# yamaHACK.net
KiCad netlist of a schematic drawn in EAGLE
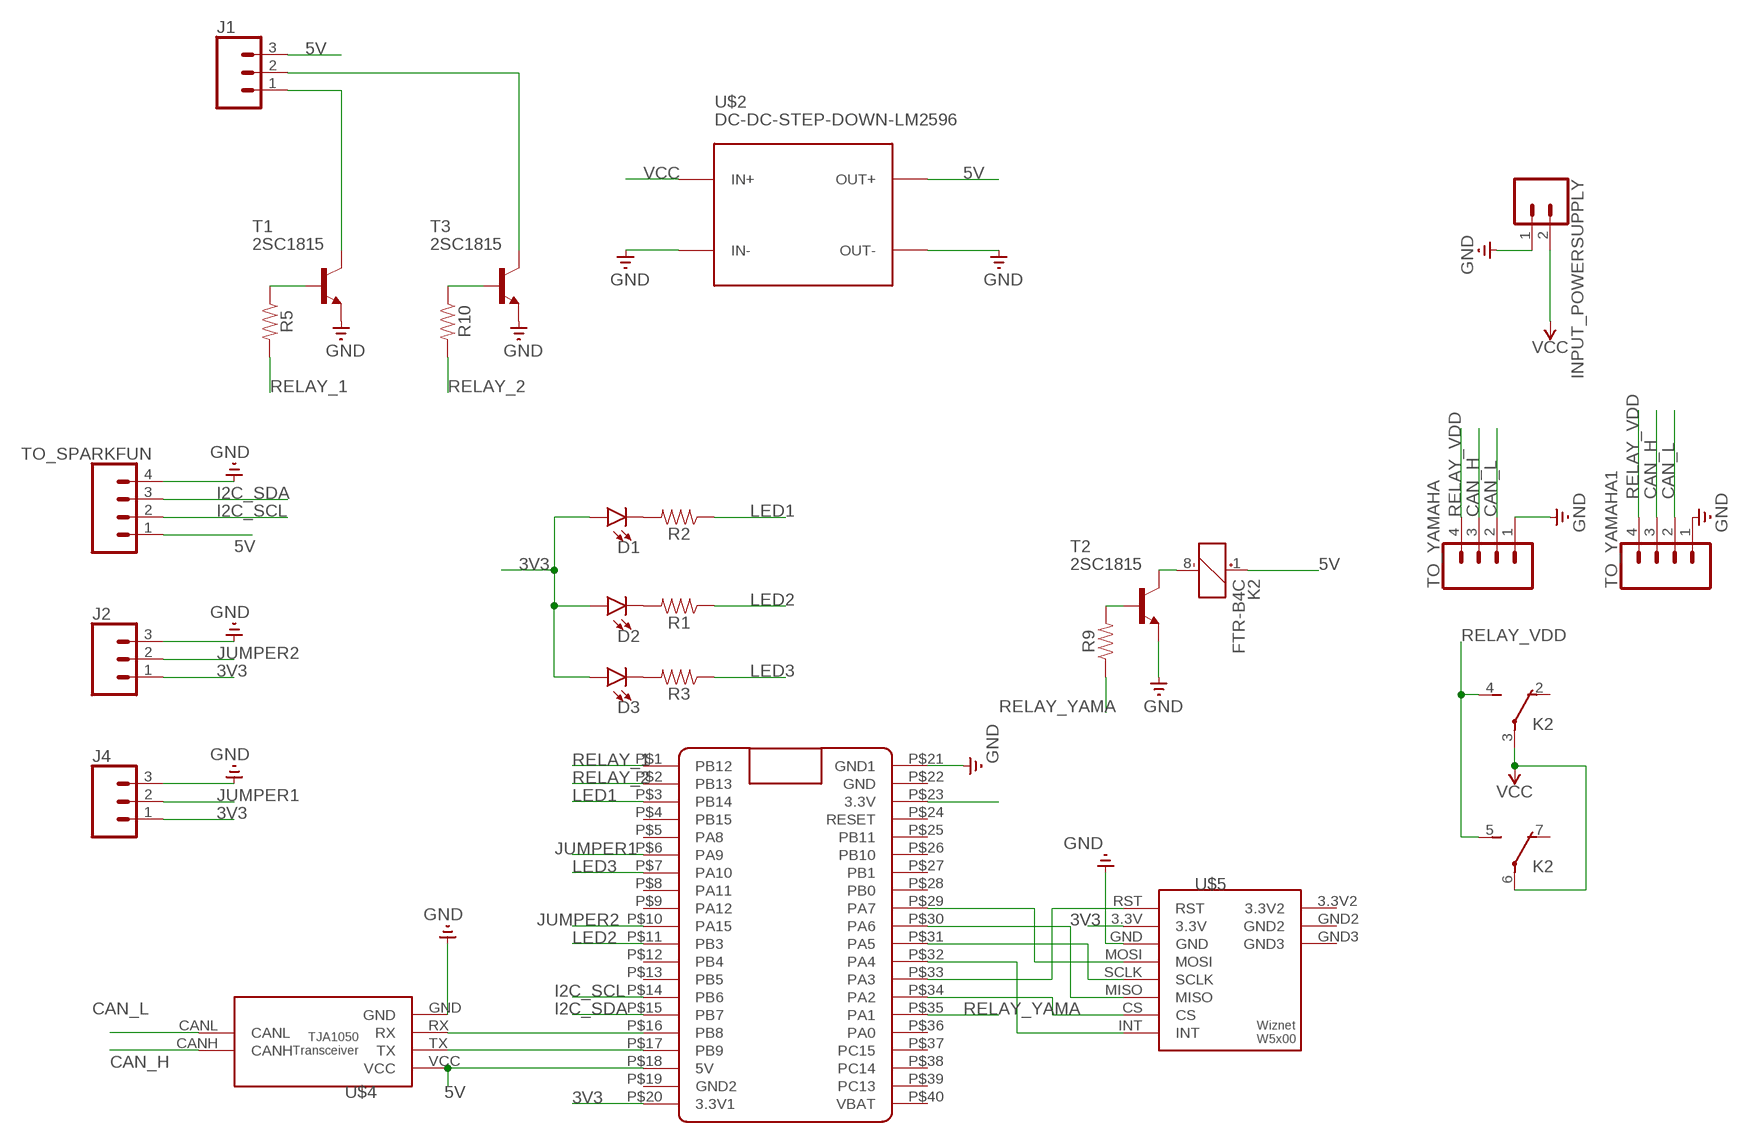
[diagram p0: schematic, sheet 1]

(export (version "E")
  (design (tool "Eeschema 10.0.6"))
  (components
    (comp (ref "D1")
      (value "LED3MM")
      (footprint "eagle-import:LED_3MM")
      (libsource (lib "eagle-import") (part "LED3MM"))
    )
    (comp (ref "D2")
      (value "LED3MM")
      (footprint "eagle-import:LED_3MM")
      (libsource (lib "eagle-import") (part "LED3MM"))
    )
    (comp (ref "D3")
      (value "LED3MM")
      (footprint "eagle-import:LED_3MM")
      (libsource (lib "eagle-import") (part "LED3MM"))
    )
    (comp (ref "INPUT_POWERSUPPLY")
      (value "CONN_02PTH3")
      (footprint "eagle-import:1X02_LONGPADS")
      (libsource (lib "eagle-import") (part "CONN_02PTH3"))
    )
    (comp (ref "J1")
      (value "CONN_03")
      (footprint "eagle-import:1X03")
      (libsource (lib "eagle-import") (part "CONN_03"))
    )
    (comp (ref "J2")
      (value "CONN_03")
      (footprint "eagle-import:1X03")
      (libsource (lib "eagle-import") (part "CONN_03"))
    )
    (comp (ref "J4")
      (value "CONN_03")
      (footprint "eagle-import:1X03")
      (libsource (lib "eagle-import") (part "CONN_03"))
    )
    (comp (ref "K2")
      (value "FTR-B4C")
      (footprint "eagle-import:FTR-B4C")
      (libsource (lib "eagle-import") (part "FTR-B4C"))
    )
    (comp (ref "R1")
      (value "RESISTORAXIAL-0.3")
      (footprint "eagle-import:AXIAL-0.3")
      (libsource (lib "eagle-import") (part "RESISTORAXIAL-0.3"))
    )
    (comp (ref "R2")
      (value "RESISTORAXIAL-0.3")
      (footprint "eagle-import:AXIAL-0.3")
      (libsource (lib "eagle-import") (part "RESISTORAXIAL-0.3"))
    )
    (comp (ref "R3")
      (value "RESISTORAXIAL-0.3")
      (footprint "eagle-import:AXIAL-0.3")
      (libsource (lib "eagle-import") (part "RESISTORAXIAL-0.3"))
    )
    (comp (ref "R5")
      (value "RESISTORAXIAL-0.3")
      (footprint "eagle-import:AXIAL-0.3")
      (libsource (lib "eagle-import") (part "RESISTORAXIAL-0.3"))
    )
    (comp (ref "R9")
      (value "RESISTORAXIAL-0.3")
      (footprint "eagle-import:AXIAL-0.3")
      (libsource (lib "eagle-import") (part "RESISTORAXIAL-0.3"))
    )
    (comp (ref "R10")
      (value "RESISTORAXIAL-0.3")
      (footprint "eagle-import:AXIAL-0.3")
      (libsource (lib "eagle-import") (part "RESISTORAXIAL-0.3"))
    )
    (comp (ref "T1")
      (value "2SC1815")
      (footprint "eagle-import:TO92-ECB")
      (libsource (lib "eagle-import") (part "2SC1815"))
    )
    (comp (ref "T2")
      (value "2SC1815")
      (footprint "eagle-import:TO92-ECB")
      (libsource (lib "eagle-import") (part "2SC1815"))
    )
    (comp (ref "T3")
      (value "2SC1815")
      (footprint "eagle-import:TO92-ECB")
      (libsource (lib "eagle-import") (part "2SC1815"))
    )
    (comp (ref "TO_SPARKFUN")
      (value "CONN_04")
      (footprint "eagle-import:1X04")
      (libsource (lib "eagle-import") (part "CONN_04"))
    )
    (comp (ref "TO_YAMAHA")
      (value "CONN_04")
      (footprint "eagle-import:1X04")
      (libsource (lib "eagle-import") (part "CONN_04"))
    )
    (comp (ref "TO_YAMAHA1")
      (value "CONN_04")
      (footprint "eagle-import:1X04")
      (libsource (lib "eagle-import") (part "CONN_04"))
    )
    (comp (ref "U$2")
      (value "DC-DC-STEP-DOWN-LM2596")
      (footprint "eagle-import:DC-DC-STEP-DOWN-LM2596")
      (libsource (lib "eagle-import") (part "DC-DC-STEP-DOWN-LM2596"))
    )
    (comp (ref "U$3")
      (value "BLUE_PILL")
      (footprint "eagle-import:BLUE_PILL")
      (libsource (lib "eagle-import") (part "BLUE_PILL"))
    )
    (comp (ref "U$4")
      (value "TJA1050TJA1050_WH")
      (footprint "eagle-import:TJA1050_WH")
      (libsource (lib "eagle-import") (part "TJA1050TJA1050_WH"))
    )
    (comp (ref "U$5")
      (value "WIZNET")
      (footprint "eagle-import:WIZNET_LITE")
      (libsource (lib "eagle-import") (part "WIZNET"))
    )
  )
  (nets
    (net (code "1") (name "/3V3") (class "Default")
      (node (ref "D1") (pin "A") (pinfunction "A_A") (pintype "passive"))
      (node (ref "D2") (pin "A") (pinfunction "A_A") (pintype "passive"))
      (node (ref "D3") (pin "A") (pinfunction "A_A") (pintype "passive"))
      (node (ref "J2") (pin "1") (pinfunction "1_1") (pintype "passive"))
      (node (ref "J4") (pin "1") (pinfunction "1_1") (pintype "passive"))
      (node (ref "U$3") (pin "P$20") (pinfunction "3.3V1_P$20") (pintype "bidirectional"))
      (node (ref "U$3") (pin "P$23") (pinfunction "3.3V_P$23") (pintype "bidirectional"))
      (node (ref "U$5") (pin "3.3V") (pinfunction "3.3V_3.3V") (pintype "bidirectional"))
    )
    (net (code "2") (name "/5V") (class "Default")
      (node (ref "J1") (pin "3") (pinfunction "3_3") (pintype "passive"))
      (node (ref "K2") (pin "1") (pinfunction "+_1") (pintype "passive"))
      (node (ref "TO_SPARKFUN") (pin "1") (pinfunction "1_1") (pintype "passive"))
      (node (ref "U$2") (pin "OUT+") (pinfunction "OUT+_OUT+") (pintype "bidirectional"))
      (node (ref "U$3") (pin "P$18") (pinfunction "5V_P$18") (pintype "bidirectional"))
      (node (ref "U$4") (pin "VCC") (pinfunction "VCC_VCC") (pintype "bidirectional"))
    )
    (net (code "3") (name "/CAN_H") (class "Default")
      (node (ref "TO_YAMAHA") (pin "3") (pinfunction "3_3") (pintype "passive"))
      (node (ref "TO_YAMAHA1") (pin "3") (pinfunction "3_3") (pintype "passive"))
      (node (ref "U$4") (pin "CANH") (pinfunction "CANH_CANH") (pintype "bidirectional"))
    )
    (net (code "4") (name "/CAN_L") (class "Default")
      (node (ref "TO_YAMAHA") (pin "2") (pinfunction "2_2") (pintype "passive"))
      (node (ref "TO_YAMAHA1") (pin "2") (pinfunction "2_2") (pintype "passive"))
      (node (ref "U$4") (pin "CANL") (pinfunction "CANL_CANL") (pintype "bidirectional"))
    )
    (net (code "5") (name "/I2C_SCL") (class "Default")
      (node (ref "TO_SPARKFUN") (pin "2") (pinfunction "2_2") (pintype "passive"))
      (node (ref "U$3") (pin "P$14") (pinfunction "PB6_P$14") (pintype "bidirectional"))
    )
    (net (code "6") (name "/I2C_SDA") (class "Default")
      (node (ref "TO_SPARKFUN") (pin "3") (pinfunction "3_3") (pintype "passive"))
      (node (ref "U$3") (pin "P$15") (pinfunction "PB7_P$15") (pintype "bidirectional"))
    )
    (net (code "7") (name "/JUMPER1") (class "Default")
      (node (ref "J4") (pin "2") (pinfunction "2_2") (pintype "passive"))
      (node (ref "U$3") (pin "P$6") (pinfunction "PA9_P$6") (pintype "bidirectional"))
    )
    (net (code "8") (name "/JUMPER2") (class "Default")
      (node (ref "J2") (pin "2") (pinfunction "2_2") (pintype "passive"))
      (node (ref "U$3") (pin "P$10") (pinfunction "PA15_P$10") (pintype "bidirectional"))
    )
    (net (code "9") (name "/LED1") (class "Default")
      (node (ref "R2") (pin "P$1") (pinfunction "1_P$1") (pintype "passive"))
      (node (ref "U$3") (pin "P$3") (pinfunction "PB14_P$3") (pintype "bidirectional"))
    )
    (net (code "10") (name "/LED2") (class "Default")
      (node (ref "R1") (pin "P$1") (pinfunction "1_P$1") (pintype "passive"))
      (node (ref "U$3") (pin "P$11") (pinfunction "PB3_P$11") (pintype "bidirectional"))
    )
    (net (code "11") (name "/LED3") (class "Default")
      (node (ref "R3") (pin "P$1") (pinfunction "1_P$1") (pintype "passive"))
      (node (ref "U$3") (pin "P$7") (pinfunction "PA10_P$7") (pintype "bidirectional"))
    )
    (net (code "12") (name "/RELAY_1") (class "Default")
      (node (ref "R5") (pin "P$2") (pinfunction "2_P$2") (pintype "passive"))
      (node (ref "U$3") (pin "P$1") (pinfunction "PB12_P$1") (pintype "bidirectional"))
    )
    (net (code "13") (name "/RELAY_2") (class "Default")
      (node (ref "R10") (pin "P$2") (pinfunction "2_P$2") (pintype "passive"))
      (node (ref "U$3") (pin "P$2") (pinfunction "PB13_P$2") (pintype "bidirectional"))
    )
    (net (code "14") (name "/RELAY_VDD") (class "Default")
      (node (ref "K2") (pin "4") (pinfunction "S_4") (pintype "passive"))
      (node (ref "K2") (pin "5") (pinfunction "S_5") (pintype "passive"))
      (node (ref "TO_YAMAHA") (pin "4") (pinfunction "4_4") (pintype "passive"))
      (node (ref "TO_YAMAHA1") (pin "4") (pinfunction "4_4") (pintype "passive"))
    )
    (net (code "15") (name "/RELAY_YAMA") (class "Default")
      (node (ref "R9") (pin "P$1") (pinfunction "1_P$1") (pintype "passive"))
      (node (ref "U$3") (pin "P$35") (pinfunction "PA1_P$35") (pintype "bidirectional"))
    )
    (net (code "16") (name "GND") (class "Default")
      (node (ref "INPUT_POWERSUPPLY") (pin "1") (pinfunction "1_1") (pintype "passive"))
      (node (ref "J2") (pin "3") (pinfunction "3_3") (pintype "passive"))
      (node (ref "J4") (pin "3") (pinfunction "3_3") (pintype "passive"))
      (node (ref "T1") (pin "E") (pinfunction "E_E") (pintype "passive"))
      (node (ref "T2") (pin "E") (pinfunction "E_E") (pintype "passive"))
      (node (ref "T3") (pin "E") (pinfunction "E_E") (pintype "passive"))
      (node (ref "TO_SPARKFUN") (pin "4") (pinfunction "4_4") (pintype "passive"))
      (node (ref "TO_YAMAHA") (pin "1") (pinfunction "1_1") (pintype "passive"))
      (node (ref "TO_YAMAHA1") (pin "1") (pinfunction "1_1") (pintype "passive"))
      (node (ref "U$2") (pin "IN-") (pinfunction "IN-_IN-") (pintype "bidirectional"))
      (node (ref "U$2") (pin "OUT-") (pinfunction "OUT-_OUT-") (pintype "bidirectional"))
      (node (ref "U$3") (pin "P$21") (pinfunction "GND1_P$21") (pintype "power_in"))
      (node (ref "U$4") (pin "GND") (pinfunction "GND_GND") (pintype "bidirectional"))
      (node (ref "U$5") (pin "GND") (pinfunction "GND_GND") (pintype "bidirectional"))
    )
    (net (code "17") (name "Net-(D1-C)") (class "Default")
      (node (ref "D1") (pin "K") (pinfunction "C_K") (pintype "passive"))
      (node (ref "R2") (pin "P$2") (pinfunction "2_P$2") (pintype "passive"))
    )
    (net (code "18") (name "Net-(D2-C)") (class "Default")
      (node (ref "D2") (pin "K") (pinfunction "C_K") (pintype "passive"))
      (node (ref "R1") (pin "P$2") (pinfunction "2_P$2") (pintype "passive"))
    )
    (net (code "19") (name "Net-(D3-C)") (class "Default")
      (node (ref "D3") (pin "K") (pinfunction "C_K") (pintype "passive"))
      (node (ref "R3") (pin "P$2") (pinfunction "2_P$2") (pintype "passive"))
    )
    (net (code "20") (name "Net-(J1-Pad1)") (class "Default")
      (node (ref "J1") (pin "1") (pinfunction "1_1") (pintype "passive"))
      (node (ref "T1") (pin "C") (pinfunction "C_C") (pintype "passive"))
    )
    (net (code "21") (name "Net-(J1-Pad2)") (class "Default")
      (node (ref "J1") (pin "2") (pinfunction "2_2") (pintype "passive"))
      (node (ref "T3") (pin "C") (pinfunction "C_C") (pintype "passive"))
    )
    (net (code "22") (name "Net-(K2C--)") (class "Default")
      (node (ref "K2") (pin "8") (pinfunction "-_8") (pintype "passive"))
      (node (ref "T2") (pin "C") (pinfunction "C_C") (pintype "passive"))
    )
    (net (code "23") (name "Net-(R5-1)") (class "Default")
      (node (ref "R5") (pin "P$1") (pinfunction "1_P$1") (pintype "passive"))
      (node (ref "T1") (pin "B") (pinfunction "B_B") (pintype "passive"))
    )
    (net (code "24") (name "Net-(R9-2)") (class "Default")
      (node (ref "R9") (pin "P$2") (pinfunction "2_P$2") (pintype "passive"))
      (node (ref "T2") (pin "B") (pinfunction "B_B") (pintype "passive"))
    )
    (net (code "25") (name "Net-(R10-1)") (class "Default")
      (node (ref "R10") (pin "P$1") (pinfunction "1_P$1") (pintype "passive"))
      (node (ref "T3") (pin "B") (pinfunction "B_B") (pintype "passive"))
    )
    (net (code "26") (name "Net-(U$3-PA2)") (class "Default")
      (node (ref "U$3") (pin "P$34") (pinfunction "PA2_P$34") (pintype "bidirectional"))
      (node (ref "U$5") (pin "CS") (pinfunction "CS_CS") (pintype "bidirectional"))
    )
    (net (code "27") (name "Net-(U$3-PA3)") (class "Default")
      (node (ref "U$3") (pin "P$33") (pinfunction "PA3_P$33") (pintype "bidirectional"))
      (node (ref "U$5") (pin "RST") (pinfunction "RST_RST") (pintype "bidirectional"))
    )
    (net (code "28") (name "Net-(U$3-PA4)") (class "Default")
      (node (ref "U$3") (pin "P$32") (pinfunction "PA4_P$32") (pintype "bidirectional"))
      (node (ref "U$5") (pin "INT") (pinfunction "INT_INT") (pintype "bidirectional"))
    )
    (net (code "29") (name "Net-(U$3-PA5)") (class "Default")
      (node (ref "U$3") (pin "P$31") (pinfunction "PA5_P$31") (pintype "bidirectional"))
      (node (ref "U$5") (pin "SCLK") (pinfunction "SCLK_SCLK") (pintype "bidirectional"))
    )
    (net (code "30") (name "Net-(U$3-PA6)") (class "Default")
      (node (ref "U$3") (pin "P$30") (pinfunction "PA6_P$30") (pintype "bidirectional"))
      (node (ref "U$5") (pin "MISO") (pinfunction "MISO_MISO") (pintype "bidirectional"))
    )
    (net (code "31") (name "Net-(U$3-PA7)") (class "Default")
      (node (ref "U$3") (pin "P$29") (pinfunction "PA7_P$29") (pintype "bidirectional"))
      (node (ref "U$5") (pin "MOSI") (pinfunction "MOSI_MOSI") (pintype "bidirectional"))
    )
    (net (code "32") (name "Net-(U$3-PB8)") (class "Default")
      (node (ref "U$3") (pin "P$16") (pinfunction "PB8_P$16") (pintype "bidirectional"))
      (node (ref "U$4") (pin "RX") (pinfunction "RX_RX") (pintype "bidirectional"))
    )
    (net (code "33") (name "Net-(U$3-PB9)") (class "Default")
      (node (ref "U$3") (pin "P$17") (pinfunction "PB9_P$17") (pintype "bidirectional"))
      (node (ref "U$4") (pin "TX") (pinfunction "TX_TX") (pintype "bidirectional"))
    )
    (net (code "34") (name "VCC") (class "Default")
      (node (ref "INPUT_POWERSUPPLY") (pin "2") (pinfunction "2_2") (pintype "passive"))
      (node (ref "K2") (pin "3") (pinfunction "P_3") (pintype "passive"))
      (node (ref "K2") (pin "6") (pinfunction "P_6") (pintype "passive"))
      (node (ref "U$2") (pin "IN+") (pinfunction "IN+_IN+") (pintype "bidirectional"))
    )
    (net (code "35") (name "unconnected-(K2A-O-Pad2)") (class "Default")
      (node (ref "K2") (pin "2") (pinfunction "O_2") (pintype "passive"))
    )
    (net (code "36") (name "unconnected-(K2B-O-Pad7)") (class "Default")
      (node (ref "K2") (pin "7") (pinfunction "O_7") (pintype "passive"))
    )
    (net (code "37") (name "unconnected-(U$3-GND-PadP$22)") (class "Default")
      (node (ref "U$3") (pin "P$22") (pinfunction "GND_P$22") (pintype "bidirectional"))
    )
    (net (code "38") (name "unconnected-(U$3-GND2-PadP$19)") (class "Default")
      (node (ref "U$3") (pin "P$19") (pinfunction "GND2_P$19") (pintype "bidirectional"))
    )
    (net (code "39") (name "unconnected-(U$3-PA0-PadP$36)") (class "Default")
      (node (ref "U$3") (pin "P$36") (pinfunction "PA0_P$36") (pintype "bidirectional"))
    )
    (net (code "40") (name "unconnected-(U$3-PA8-PadP$5)") (class "Default")
      (node (ref "U$3") (pin "P$5") (pinfunction "PA8_P$5") (pintype "bidirectional"))
    )
    (net (code "41") (name "unconnected-(U$3-PA11-PadP$8)") (class "Default")
      (node (ref "U$3") (pin "P$8") (pinfunction "PA11_P$8") (pintype "bidirectional"))
    )
    (net (code "42") (name "unconnected-(U$3-PA12-PadP$9)") (class "Default")
      (node (ref "U$3") (pin "P$9") (pinfunction "PA12_P$9") (pintype "bidirectional"))
    )
    (net (code "43") (name "unconnected-(U$3-PB0-PadP$28)") (class "Default")
      (node (ref "U$3") (pin "P$28") (pinfunction "PB0_P$28") (pintype "bidirectional"))
    )
    (net (code "44") (name "unconnected-(U$3-PB1-PadP$27)") (class "Default")
      (node (ref "U$3") (pin "P$27") (pinfunction "PB1_P$27") (pintype "bidirectional"))
    )
    (net (code "45") (name "unconnected-(U$3-PB4-PadP$12)") (class "Default")
      (node (ref "U$3") (pin "P$12") (pinfunction "PB4_P$12") (pintype "bidirectional"))
    )
    (net (code "46") (name "unconnected-(U$3-PB5-PadP$13)") (class "Default")
      (node (ref "U$3") (pin "P$13") (pinfunction "PB5_P$13") (pintype "bidirectional"))
    )
    (net (code "47") (name "unconnected-(U$3-PB10-PadP$26)") (class "Default")
      (node (ref "U$3") (pin "P$26") (pinfunction "PB10_P$26") (pintype "bidirectional"))
    )
    (net (code "48") (name "unconnected-(U$3-PB11-PadP$25)") (class "Default")
      (node (ref "U$3") (pin "P$25") (pinfunction "PB11_P$25") (pintype "bidirectional"))
    )
    (net (code "49") (name "unconnected-(U$3-PB15-PadP$4)") (class "Default")
      (node (ref "U$3") (pin "P$4") (pinfunction "PB15_P$4") (pintype "bidirectional"))
    )
    (net (code "50") (name "unconnected-(U$3-PC13-PadP$39)") (class "Default")
      (node (ref "U$3") (pin "P$39") (pinfunction "PC13_P$39") (pintype "bidirectional"))
    )
    (net (code "51") (name "unconnected-(U$3-PC14-PadP$38)") (class "Default")
      (node (ref "U$3") (pin "P$38") (pinfunction "PC14_P$38") (pintype "bidirectional"))
    )
    (net (code "52") (name "unconnected-(U$3-PC15-PadP$37)") (class "Default")
      (node (ref "U$3") (pin "P$37") (pinfunction "PC15_P$37") (pintype "bidirectional"))
    )
    (net (code "53") (name "unconnected-(U$3-RESET-PadP$24)") (class "Default")
      (node (ref "U$3") (pin "P$24") (pinfunction "RESET_P$24") (pintype "bidirectional"))
    )
    (net (code "54") (name "unconnected-(U$3-VBAT-PadP$40)") (class "Default")
      (node (ref "U$3") (pin "P$40") (pinfunction "VBAT_P$40") (pintype "bidirectional"))
    )
    (net (code "55") (name "unconnected-(U$5-Pad3.3V2)") (class "Default")
      (node (ref "U$5") (pin "3.3V2") (pinfunction "3.3V2_3.3V2") (pintype "bidirectional"))
    )
    (net (code "56") (name "unconnected-(U$5-PadGND2)") (class "Default")
      (node (ref "U$5") (pin "GND2") (pinfunction "GND2_GND2") (pintype "bidirectional"))
    )
    (net (code "57") (name "unconnected-(U$5-PadGND3)") (class "Default")
      (node (ref "U$5") (pin "GND3") (pinfunction "GND3_GND3") (pintype "bidirectional"))
    )
  )
)
